# STM32F407VG_B.net
KiCad netlist of a schematic drawn in Altium Designer
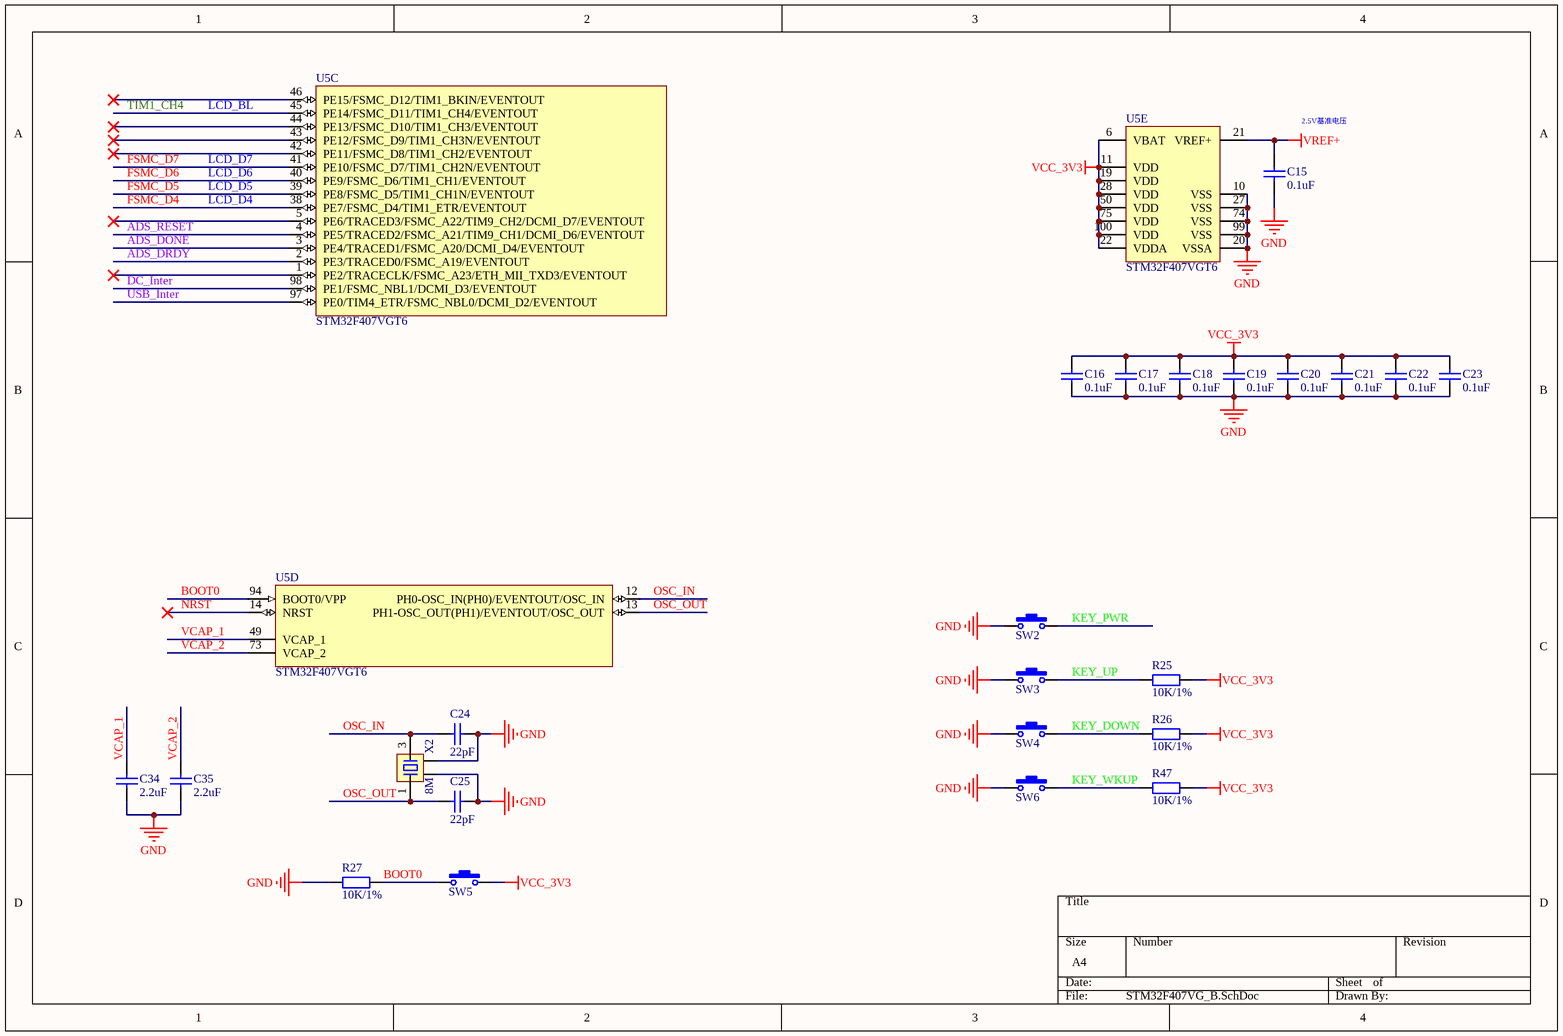
[diagram p0: STM32F407VG_B.SchDoc]

(export (version "E")
  (design (tool "Eeschema 10.0.6"))
  (components
    (comp (ref "C15")
      (value "0.1uF")
      (footprint "C0402_L")
      (description "贴片电容")
      (libsource (lib "0.1 - 电阻-电容-电感-晶振-晶体-磁珠-电位器") (part "C"))
    )
    (comp (ref "C16")
      (value "0.1uF")
      (footprint "C0402_L")
      (description "贴片电容")
      (libsource (lib "0.1 - 电阻-电容-电感-晶振-晶体-磁珠-电位器") (part "C"))
    )
    (comp (ref "C17")
      (value "0.1uF")
      (footprint "C0402_L")
      (description "贴片电容")
      (libsource (lib "0.1 - 电阻-电容-电感-晶振-晶体-磁珠-电位器") (part "C"))
    )
    (comp (ref "C18")
      (value "0.1uF")
      (footprint "C0402_L")
      (description "贴片电容")
      (libsource (lib "0.1 - 电阻-电容-电感-晶振-晶体-磁珠-电位器") (part "C"))
    )
    (comp (ref "C19")
      (value "0.1uF")
      (footprint "C0402_L")
      (description "贴片电容")
      (libsource (lib "0.1 - 电阻-电容-电感-晶振-晶体-磁珠-电位器") (part "C"))
    )
    (comp (ref "C20")
      (value "0.1uF")
      (footprint "C0402_L")
      (description "贴片电容")
      (libsource (lib "0.1 - 电阻-电容-电感-晶振-晶体-磁珠-电位器") (part "C"))
    )
    (comp (ref "C21")
      (value "0.1uF")
      (footprint "C0402_L")
      (description "贴片电容")
      (libsource (lib "0.1 - 电阻-电容-电感-晶振-晶体-磁珠-电位器") (part "C"))
    )
    (comp (ref "C22")
      (value "0.1uF")
      (footprint "C0402_L")
      (description "贴片电容")
      (libsource (lib "0.1 - 电阻-电容-电感-晶振-晶体-磁珠-电位器") (part "C"))
    )
    (comp (ref "C23")
      (value "0.1uF")
      (footprint "C0402_L")
      (description "贴片电容")
      (libsource (lib "0.1 - 电阻-电容-电感-晶振-晶体-磁珠-电位器") (part "C"))
    )
    (comp (ref "C24")
      (value "22pF")
      (footprint "C0402_L")
      (description "贴片电容")
      (libsource (lib "0.1 - 电阻-电容-电感-晶振-晶体-磁珠-电位器") (part "C"))
    )
    (comp (ref "C25")
      (value "22pF")
      (footprint "C0402_L")
      (description "贴片电容")
      (libsource (lib "0.1 - 电阻-电容-电感-晶振-晶体-磁珠-电位器") (part "C"))
    )
    (comp (ref "C34")
      (value "2.2uF")
      (footprint "C0402_L")
      (description "贴片电容")
      (libsource (lib "0.1 - 电阻-电容-电感-晶振-晶体-磁珠-电位器") (part "C"))
    )
    (comp (ref "C35")
      (value "2.2uF")
      (footprint "C0402_L")
      (description "贴片电容")
      (libsource (lib "0.1 - 电阻-电容-电感-晶振-晶体-磁珠-电位器") (part "C"))
    )
    (comp (ref "R25")
      (value "10K/1%")
      (footprint "R0402_L")
      (description "贴片电阻")
      (libsource (lib "0.1 - 电阻-电容-电感-晶振-晶体-磁珠-电位器") (part "R"))
    )
    (comp (ref "R26")
      (value "10K/1%")
      (footprint "R0402_L")
      (description "贴片电阻")
      (libsource (lib "0.1 - 电阻-电容-电感-晶振-晶体-磁珠-电位器") (part "R"))
    )
    (comp (ref "R27")
      (value "10K/1%")
      (footprint "R0402_L")
      (description "贴片电阻")
      (libsource (lib "0.1 - 电阻-电容-电感-晶振-晶体-磁珠-电位器") (part "R"))
    )
    (comp (ref "R47")
      (value "10K/1%")
      (footprint "R0402_L")
      (description "贴片电阻")
      (libsource (lib "0.1 - 电阻-电容-电感-晶振-晶体-磁珠-电位器") (part "R"))
    )
    (comp (ref "SW2")
      (value "小龟按键")
      (footprint "2*4*3.5")
      (description "微动开关")
      (libsource (lib "0.5 - 按键-开关-蜂鸣器-保险丝-电池-测试点-Mark点") (part "SW-PB"))
    )
    (comp (ref "SW3")
      (value "小龟按键")
      (footprint "2*4*3.5")
      (description "微动开关")
      (libsource (lib "0.5 - 按键-开关-蜂鸣器-保险丝-电池-测试点-Mark点") (part "SW-PB"))
    )
    (comp (ref "SW4")
      (value "小龟按键")
      (footprint "2*4*3.5")
      (description "微动开关")
      (libsource (lib "0.5 - 按键-开关-蜂鸣器-保险丝-电池-测试点-Mark点") (part "SW-PB"))
    )
    (comp (ref "SW5")
      (value "小龟按键")
      (footprint "3*4两脚小龟按键")
      (description "微动开关")
      (libsource (lib "0.5 - 按键-开关-蜂鸣器-保险丝-电池-测试点-Mark点") (part "SW-PB"))
    )
    (comp (ref "SW6")
      (value "小龟按键")
      (footprint "2*4*3.5")
      (description "微动开关")
      (libsource (lib "0.5 - 按键-开关-蜂鸣器-保险丝-电池-测试点-Mark点") (part "SW-PB"))
    )
    (comp (ref "U5")
      (value "STM32F407VGT6")
      (footprint "LQFP100_L")
      (libsource (lib "2.7 - STM32 F4系列单片机") (part "STM32F407VGT6"))
    )
    (comp (ref "X2")
      (value "8M")
      (footprint "XTAL-3225-4P")
      (description "4脚无源晶振(谐振器）")
      (libsource (lib "0.1 - 电阻-电容-电感-晶振-晶体-磁珠-电位器") (part "XTAL-4P"))
    )
  )
  (nets
    (net (code "1") (name "/ADS_DONE") (class "Default")
      (node (ref "U5") (pin "3") (pinfunction "PE4/TRACED1/FSMC_A20/DCMI_D4/EVENTOUT_3") (pintype "bidirectional"))
    )
    (net (code "2") (name "/ADS_DRDY") (class "Default")
      (node (ref "U5") (pin "2") (pinfunction "PE3/TRACED0/FSMC_A19/EVENTOUT_2") (pintype "bidirectional"))
    )
    (net (code "3") (name "/ADS_RESET") (class "Default")
      (node (ref "U5") (pin "4") (pinfunction "PE5/TRACED2/FSMC_A21/TIM9_CH1/DCMI_D6/EVENTOUT_4") (pintype "bidirectional"))
    )
    (net (code "4") (name "/BOOT0") (class "Default")
      (node (ref "R27") (pin "2") (pinfunction "2_2") (pintype "passive"))
      (node (ref "SW5") (pin "1") (pinfunction "1_1") (pintype "passive"))
      (node (ref "U5") (pin "94") (pinfunction "BOOT0/VPP_94") (pintype "input"))
    )
    (net (code "5") (name "/DC_Inter") (class "Default")
      (node (ref "U5") (pin "98") (pinfunction "PE1/FSMC_NBL1/DCMI_D3/EVENTOUT_98") (pintype "bidirectional"))
    )
    (net (code "6") (name "/FSMC_D4") (class "Default")
      (node (ref "U5") (pin "38") (pinfunction "PE7/FSMC_D4/TIM1_ETR/EVENTOUT_38") (pintype "bidirectional"))
    )
    (net (code "7") (name "/FSMC_D5") (class "Default")
      (node (ref "U5") (pin "39") (pinfunction "PE8/FSMC_D5/TIM1_CH1N/EVENTOUT_39") (pintype "bidirectional"))
    )
    (net (code "8") (name "/FSMC_D6") (class "Default")
      (node (ref "U5") (pin "40") (pinfunction "PE9/FSMC_D6/TIM1_CH1/EVENTOUT_40") (pintype "bidirectional"))
    )
    (net (code "9") (name "/FSMC_D7") (class "Default")
      (node (ref "U5") (pin "41") (pinfunction "PE10/FSMC_D7/TIM1_CH2N/EVENTOUT_41") (pintype "bidirectional"))
    )
    (net (code "10") (name "/KEY_DOWN") (class "Default")
      (node (ref "R26") (pin "1") (pinfunction "1_1") (pintype "passive"))
      (node (ref "SW4") (pin "2") (pinfunction "2_2") (pintype "passive"))
    )
    (net (code "11") (name "/KEY_PWR") (class "Default")
      (node (ref "SW2") (pin "2") (pinfunction "2_2") (pintype "passive"))
    )
    (net (code "12") (name "/KEY_UP") (class "Default")
      (node (ref "R25") (pin "1") (pinfunction "1_1") (pintype "passive"))
      (node (ref "SW3") (pin "2") (pinfunction "2_2") (pintype "passive"))
    )
    (net (code "13") (name "/KEY_WKUP") (class "Default")
      (node (ref "R47") (pin "1") (pinfunction "1_1") (pintype "passive"))
      (node (ref "SW6") (pin "2") (pinfunction "2_2") (pintype "passive"))
    )
    (net (code "14") (name "/LCD_BL") (class "Default")
      (node (ref "U5") (pin "45") (pinfunction "PE14/FSMC_D11/TIM1_CH4/EVENTOUT_45") (pintype "bidirectional"))
    )
    (net (code "15") (name "/NRST") (class "Default")
      (node (ref "U5") (pin "14") (pinfunction "NRST_14") (pintype "bidirectional+no_connect"))
    )
    (net (code "16") (name "/OSC_IN") (class "Default")
      (node (ref "C24") (pin "1") (pinfunction "1_1") (pintype "passive"))
      (node (ref "U5") (pin "12") (pinfunction "PH0-OSC_IN(PH0)/EVENTOUT/OSC_IN_12") (pintype "bidirectional"))
      (node (ref "X2") (pin "3") (pinfunction "3_3") (pintype "passive"))
    )
    (net (code "17") (name "/OSC_OUT") (class "Default")
      (node (ref "C25") (pin "1") (pinfunction "1_1") (pintype "passive"))
      (node (ref "U5") (pin "13") (pinfunction "PH1-OSC_OUT(PH1)/EVENTOUT/OSC_OUT_13") (pintype "bidirectional"))
      (node (ref "X2") (pin "1") (pinfunction "1_1") (pintype "passive"))
    )
    (net (code "18") (name "/USB_Inter") (class "Default")
      (node (ref "U5") (pin "97") (pinfunction "PE0/TIM4_ETR/FSMC_NBL0/DCMI_D2/EVENTOUT_97") (pintype "bidirectional"))
    )
    (net (code "19") (name "/VCAP_1") (class "Default")
      (node (ref "C34") (pin "2") (pinfunction "2_2") (pintype "passive"))
      (node (ref "U5") (pin "49") (pinfunction "VCAP_1_49") (pintype "power_in"))
    )
    (net (code "20") (name "/VCAP_2") (class "Default")
      (node (ref "C35") (pin "2") (pinfunction "2_2") (pintype "passive"))
      (node (ref "U5") (pin "73") (pinfunction "VCAP_2_73") (pintype "power_in"))
    )
    (net (code "21") (name "GND") (class "Default")
      (node (ref "C15") (pin "1") (pinfunction "1_1") (pintype "passive"))
      (node (ref "C16") (pin "1") (pinfunction "1_1") (pintype "passive"))
      (node (ref "C17") (pin "1") (pinfunction "1_1") (pintype "passive"))
      (node (ref "C18") (pin "1") (pinfunction "1_1") (pintype "passive"))
      (node (ref "C19") (pin "1") (pinfunction "1_1") (pintype "passive"))
      (node (ref "C20") (pin "1") (pinfunction "1_1") (pintype "passive"))
      (node (ref "C21") (pin "1") (pinfunction "1_1") (pintype "passive"))
      (node (ref "C22") (pin "1") (pinfunction "1_1") (pintype "passive"))
      (node (ref "C23") (pin "1") (pinfunction "1_1") (pintype "passive"))
      (node (ref "C24") (pin "2") (pinfunction "2_2") (pintype "passive"))
      (node (ref "C25") (pin "2") (pinfunction "2_2") (pintype "passive"))
      (node (ref "C34") (pin "1") (pinfunction "1_1") (pintype "passive"))
      (node (ref "C35") (pin "1") (pinfunction "1_1") (pintype "passive"))
      (node (ref "R27") (pin "1") (pinfunction "1_1") (pintype "passive"))
      (node (ref "SW2") (pin "1") (pinfunction "1_1") (pintype "passive"))
      (node (ref "SW3") (pin "1") (pinfunction "1_1") (pintype "passive"))
      (node (ref "SW4") (pin "1") (pinfunction "1_1") (pintype "passive"))
      (node (ref "SW6") (pin "1") (pinfunction "1_1") (pintype "passive"))
      (node (ref "U5") (pin "10") (pinfunction "VSS_10") (pintype "power_in"))
      (node (ref "U5") (pin "20") (pinfunction "VSSA_20") (pintype "power_in"))
      (node (ref "U5") (pin "27") (pinfunction "VSS_27") (pintype "power_in"))
      (node (ref "U5") (pin "74") (pinfunction "VSS_74") (pintype "power_in"))
      (node (ref "U5") (pin "99") (pinfunction "VSS_99") (pintype "power_in"))
      (node (ref "X2") (pin "2") (pinfunction "2_2") (pintype "passive"))
      (node (ref "X2") (pin "4") (pinfunction "4_4") (pintype "passive"))
    )
    (net (code "22") (name "VCC_3V3") (class "Default")
      (node (ref "C16") (pin "2") (pinfunction "2_2") (pintype "passive"))
      (node (ref "C17") (pin "2") (pinfunction "2_2") (pintype "passive"))
      (node (ref "C18") (pin "2") (pinfunction "2_2") (pintype "passive"))
      (node (ref "C19") (pin "2") (pinfunction "2_2") (pintype "passive"))
      (node (ref "C20") (pin "2") (pinfunction "2_2") (pintype "passive"))
      (node (ref "C21") (pin "2") (pinfunction "2_2") (pintype "passive"))
      (node (ref "C22") (pin "2") (pinfunction "2_2") (pintype "passive"))
      (node (ref "C23") (pin "2") (pinfunction "2_2") (pintype "passive"))
      (node (ref "R25") (pin "2") (pinfunction "2_2") (pintype "passive"))
      (node (ref "R26") (pin "2") (pinfunction "2_2") (pintype "passive"))
      (node (ref "R47") (pin "2") (pinfunction "2_2") (pintype "passive"))
      (node (ref "SW5") (pin "2") (pinfunction "2_2") (pintype "passive"))
      (node (ref "U5") (pin "100") (pinfunction "VDD_100") (pintype "power_in"))
      (node (ref "U5") (pin "11") (pinfunction "VDD_11") (pintype "power_in"))
      (node (ref "U5") (pin "19") (pinfunction "VDD_19") (pintype "power_in"))
      (node (ref "U5") (pin "22") (pinfunction "VDDA_22") (pintype "power_in"))
      (node (ref "U5") (pin "28") (pinfunction "VDD_28") (pintype "power_in"))
      (node (ref "U5") (pin "50") (pinfunction "VDD_50") (pintype "power_in"))
      (node (ref "U5") (pin "6") (pinfunction "VBAT_6") (pintype "power_in"))
      (node (ref "U5") (pin "75") (pinfunction "VDD_75") (pintype "power_in"))
    )
    (net (code "23") (name "VREF+") (class "Default")
      (node (ref "C15") (pin "2") (pinfunction "2_2") (pintype "passive"))
      (node (ref "U5") (pin "21") (pinfunction "VREF+_21") (pintype "power_in"))
    )
    (net (code "24") (name "unconnected-(U5C-PE2{slash}TRACECLK{slash}FSMC_A23{slash}ETH_MII_TXD3{slash}EVENTOUT-Pad1)") (class "Default")
      (node (ref "U5") (pin "1") (pinfunction "PE2/TRACECLK/FSMC_A23/ETH_MII_TXD3/EVENTOUT_1") (pintype "bidirectional+no_connect"))
    )
    (net (code "25") (name "unconnected-(U5C-PE6{slash}TRACED3{slash}FSMC_A22{slash}TIM9_CH2{slash}DCMI_D7{slash}EVENTOUT-Pad5)") (class "Default")
      (node (ref "U5") (pin "5") (pinfunction "PE6/TRACED3/FSMC_A22/TIM9_CH2/DCMI_D7/EVENTOUT_5") (pintype "bidirectional+no_connect"))
    )
    (net (code "26") (name "unconnected-(U5C-PE11{slash}FSMC_D8{slash}TIM1_CH2{slash}EVENTOUT-Pad42)") (class "Default")
      (node (ref "U5") (pin "42") (pinfunction "PE11/FSMC_D8/TIM1_CH2/EVENTOUT_42") (pintype "bidirectional+no_connect"))
    )
    (net (code "27") (name "unconnected-(U5C-PE12{slash}FSMC_D9{slash}TIM1_CH3N{slash}EVENTOUT-Pad43)") (class "Default")
      (node (ref "U5") (pin "43") (pinfunction "PE12/FSMC_D9/TIM1_CH3N/EVENTOUT_43") (pintype "bidirectional+no_connect"))
    )
    (net (code "28") (name "unconnected-(U5C-PE13{slash}FSMC_D10{slash}TIM1_CH3{slash}EVENTOUT-Pad44)") (class "Default")
      (node (ref "U5") (pin "44") (pinfunction "PE13/FSMC_D10/TIM1_CH3/EVENTOUT_44") (pintype "bidirectional+no_connect"))
    )
    (net (code "29") (name "unconnected-(U5C-PE15{slash}FSMC_D12{slash}TIM1_BKIN{slash}EVENTOUT-Pad46)") (class "Default")
      (node (ref "U5") (pin "46") (pinfunction "PE15/FSMC_D12/TIM1_BKIN/EVENTOUT_46") (pintype "bidirectional+no_connect"))
    )
  )
)
